# TQFP-DIP.net
KiCad netlist of a schematic drawn in EAGLE
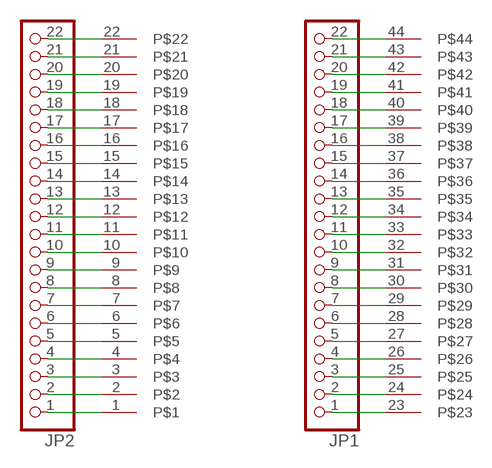
[diagram p0: schematic, sheet 1]

(export (version "E")
  (design (tool "Eeschema 10.0.6"))
  (components
    (comp (ref "JP1")
      (value "PINHD-1X22")
      (footprint "eagle-import:1X22")
      (libsource (lib "eagle-import") (part "PINHD-1X22"))
    )
    (comp (ref "JP2")
      (value "PINHD-1X22")
      (footprint "eagle-import:1X22")
      (libsource (lib "eagle-import") (part "PINHD-1X22"))
    )
    (comp (ref "U$1")
      (value "TQFP44")
      (footprint "eagle-import:TQFP44")
      (libsource (lib "eagle-import") (part "TQFP44"))
    )
  )
  (nets
    (net (code "1") (name "Net-(U$1-P$1)") (class "Default")
      (node (ref "JP2") (pin "1") (pinfunction "1_1") (pintype "passive"))
      (node (ref "U$1") (pin "1") (pinfunction "P$1_1") (pintype "bidirectional"))
    )
    (net (code "2") (name "Net-(U$1-P$2)") (class "Default")
      (node (ref "JP2") (pin "2") (pinfunction "2_2") (pintype "passive"))
      (node (ref "U$1") (pin "2") (pinfunction "P$2_2") (pintype "bidirectional"))
    )
    (net (code "3") (name "Net-(U$1-P$3)") (class "Default")
      (node (ref "JP2") (pin "3") (pinfunction "3_3") (pintype "passive"))
      (node (ref "U$1") (pin "3") (pinfunction "P$3_3") (pintype "bidirectional"))
    )
    (net (code "4") (name "Net-(U$1-P$4)") (class "Default")
      (node (ref "JP2") (pin "4") (pinfunction "4_4") (pintype "passive"))
      (node (ref "U$1") (pin "4") (pinfunction "P$4_4") (pintype "bidirectional"))
    )
    (net (code "5") (name "Net-(U$1-P$5)") (class "Default")
      (node (ref "JP2") (pin "5") (pinfunction "5_5") (pintype "passive"))
      (node (ref "U$1") (pin "5") (pinfunction "P$5_5") (pintype "bidirectional"))
    )
    (net (code "6") (name "Net-(U$1-P$6)") (class "Default")
      (node (ref "JP2") (pin "6") (pinfunction "6_6") (pintype "passive"))
      (node (ref "U$1") (pin "6") (pinfunction "P$6_6") (pintype "bidirectional"))
    )
    (net (code "7") (name "Net-(U$1-P$7)") (class "Default")
      (node (ref "JP2") (pin "7") (pinfunction "7_7") (pintype "passive"))
      (node (ref "U$1") (pin "7") (pinfunction "P$7_7") (pintype "bidirectional"))
    )
    (net (code "8") (name "Net-(U$1-P$8)") (class "Default")
      (node (ref "JP2") (pin "8") (pinfunction "8_8") (pintype "passive"))
      (node (ref "U$1") (pin "8") (pinfunction "P$8_8") (pintype "bidirectional"))
    )
    (net (code "9") (name "Net-(U$1-P$9)") (class "Default")
      (node (ref "JP2") (pin "9") (pinfunction "9_9") (pintype "passive"))
      (node (ref "U$1") (pin "9") (pinfunction "P$9_9") (pintype "bidirectional"))
    )
    (net (code "10") (name "Net-(U$1-P$10)") (class "Default")
      (node (ref "JP2") (pin "10") (pinfunction "10_10") (pintype "passive"))
      (node (ref "U$1") (pin "10") (pinfunction "P$10_10") (pintype "bidirectional"))
    )
    (net (code "11") (name "Net-(U$1-P$11)") (class "Default")
      (node (ref "JP2") (pin "11") (pinfunction "11_11") (pintype "passive"))
      (node (ref "U$1") (pin "11") (pinfunction "P$11_11") (pintype "bidirectional"))
    )
    (net (code "12") (name "Net-(U$1-P$12)") (class "Default")
      (node (ref "JP2") (pin "12") (pinfunction "12_12") (pintype "passive"))
      (node (ref "U$1") (pin "12") (pinfunction "P$12_12") (pintype "bidirectional"))
    )
    (net (code "13") (name "Net-(U$1-P$13)") (class "Default")
      (node (ref "JP2") (pin "13") (pinfunction "13_13") (pintype "passive"))
      (node (ref "U$1") (pin "13") (pinfunction "P$13_13") (pintype "bidirectional"))
    )
    (net (code "14") (name "Net-(U$1-P$14)") (class "Default")
      (node (ref "JP2") (pin "14") (pinfunction "14_14") (pintype "passive"))
      (node (ref "U$1") (pin "14") (pinfunction "P$14_14") (pintype "bidirectional"))
    )
    (net (code "15") (name "Net-(U$1-P$15)") (class "Default")
      (node (ref "JP2") (pin "15") (pinfunction "15_15") (pintype "passive"))
      (node (ref "U$1") (pin "15") (pinfunction "P$15_15") (pintype "bidirectional"))
    )
    (net (code "16") (name "Net-(U$1-P$16)") (class "Default")
      (node (ref "JP2") (pin "16") (pinfunction "16_16") (pintype "passive"))
      (node (ref "U$1") (pin "16") (pinfunction "P$16_16") (pintype "bidirectional"))
    )
    (net (code "17") (name "Net-(U$1-P$17)") (class "Default")
      (node (ref "JP2") (pin "17") (pinfunction "17_17") (pintype "passive"))
      (node (ref "U$1") (pin "17") (pinfunction "P$17_17") (pintype "bidirectional"))
    )
    (net (code "18") (name "Net-(U$1-P$18)") (class "Default")
      (node (ref "JP2") (pin "18") (pinfunction "18_18") (pintype "passive"))
      (node (ref "U$1") (pin "18") (pinfunction "P$18_18") (pintype "bidirectional"))
    )
    (net (code "19") (name "Net-(U$1-P$19)") (class "Default")
      (node (ref "JP2") (pin "19") (pinfunction "19_19") (pintype "passive"))
      (node (ref "U$1") (pin "19") (pinfunction "P$19_19") (pintype "bidirectional"))
    )
    (net (code "20") (name "Net-(U$1-P$20)") (class "Default")
      (node (ref "JP2") (pin "20") (pinfunction "20_20") (pintype "passive"))
      (node (ref "U$1") (pin "20") (pinfunction "P$20_20") (pintype "bidirectional"))
    )
    (net (code "21") (name "Net-(U$1-P$21)") (class "Default")
      (node (ref "JP2") (pin "21") (pinfunction "21_21") (pintype "passive"))
      (node (ref "U$1") (pin "21") (pinfunction "P$21_21") (pintype "bidirectional"))
    )
    (net (code "22") (name "Net-(U$1-P$22)") (class "Default")
      (node (ref "JP2") (pin "22") (pinfunction "22_22") (pintype "passive"))
      (node (ref "U$1") (pin "22") (pinfunction "P$22_22") (pintype "bidirectional"))
    )
    (net (code "23") (name "Net-(U$1-P$23)") (class "Default")
      (node (ref "JP1") (pin "1") (pinfunction "1_1") (pintype "passive"))
      (node (ref "U$1") (pin "23") (pinfunction "P$23_23") (pintype "bidirectional"))
    )
    (net (code "24") (name "Net-(U$1-P$24)") (class "Default")
      (node (ref "JP1") (pin "2") (pinfunction "2_2") (pintype "passive"))
      (node (ref "U$1") (pin "24") (pinfunction "P$24_24") (pintype "bidirectional"))
    )
    (net (code "25") (name "Net-(U$1-P$25)") (class "Default")
      (node (ref "JP1") (pin "3") (pinfunction "3_3") (pintype "passive"))
      (node (ref "U$1") (pin "25") (pinfunction "P$25_25") (pintype "bidirectional"))
    )
    (net (code "26") (name "Net-(U$1-P$26)") (class "Default")
      (node (ref "JP1") (pin "4") (pinfunction "4_4") (pintype "passive"))
      (node (ref "U$1") (pin "26") (pinfunction "P$26_26") (pintype "bidirectional"))
    )
    (net (code "27") (name "Net-(U$1-P$27)") (class "Default")
      (node (ref "JP1") (pin "5") (pinfunction "5_5") (pintype "passive"))
      (node (ref "U$1") (pin "27") (pinfunction "P$27_27") (pintype "bidirectional"))
    )
    (net (code "28") (name "Net-(U$1-P$28)") (class "Default")
      (node (ref "JP1") (pin "6") (pinfunction "6_6") (pintype "passive"))
      (node (ref "U$1") (pin "28") (pinfunction "P$28_28") (pintype "bidirectional"))
    )
    (net (code "29") (name "Net-(U$1-P$29)") (class "Default")
      (node (ref "JP1") (pin "7") (pinfunction "7_7") (pintype "passive"))
      (node (ref "U$1") (pin "29") (pinfunction "P$29_29") (pintype "bidirectional"))
    )
    (net (code "30") (name "Net-(U$1-P$30)") (class "Default")
      (node (ref "JP1") (pin "8") (pinfunction "8_8") (pintype "passive"))
      (node (ref "U$1") (pin "30") (pinfunction "P$30_30") (pintype "bidirectional"))
    )
    (net (code "31") (name "Net-(U$1-P$31)") (class "Default")
      (node (ref "JP1") (pin "9") (pinfunction "9_9") (pintype "passive"))
      (node (ref "U$1") (pin "31") (pinfunction "P$31_31") (pintype "bidirectional"))
    )
    (net (code "32") (name "Net-(U$1-P$32)") (class "Default")
      (node (ref "JP1") (pin "10") (pinfunction "10_10") (pintype "passive"))
      (node (ref "U$1") (pin "32") (pinfunction "P$32_32") (pintype "bidirectional"))
    )
    (net (code "33") (name "Net-(U$1-P$33)") (class "Default")
      (node (ref "JP1") (pin "11") (pinfunction "11_11") (pintype "passive"))
      (node (ref "U$1") (pin "33") (pinfunction "P$33_33") (pintype "bidirectional"))
    )
    (net (code "34") (name "Net-(U$1-P$34)") (class "Default")
      (node (ref "JP1") (pin "12") (pinfunction "12_12") (pintype "passive"))
      (node (ref "U$1") (pin "34") (pinfunction "P$34_34") (pintype "bidirectional"))
    )
    (net (code "35") (name "Net-(U$1-P$35)") (class "Default")
      (node (ref "JP1") (pin "13") (pinfunction "13_13") (pintype "passive"))
      (node (ref "U$1") (pin "35") (pinfunction "P$35_35") (pintype "bidirectional"))
    )
    (net (code "36") (name "Net-(U$1-P$36)") (class "Default")
      (node (ref "JP1") (pin "14") (pinfunction "14_14") (pintype "passive"))
      (node (ref "U$1") (pin "36") (pinfunction "P$36_36") (pintype "bidirectional"))
    )
    (net (code "37") (name "Net-(U$1-P$37)") (class "Default")
      (node (ref "JP1") (pin "15") (pinfunction "15_15") (pintype "passive"))
      (node (ref "U$1") (pin "37") (pinfunction "P$37_37") (pintype "bidirectional"))
    )
    (net (code "38") (name "Net-(U$1-P$38)") (class "Default")
      (node (ref "JP1") (pin "16") (pinfunction "16_16") (pintype "passive"))
      (node (ref "U$1") (pin "38") (pinfunction "P$38_38") (pintype "bidirectional"))
    )
    (net (code "39") (name "Net-(U$1-P$39)") (class "Default")
      (node (ref "JP1") (pin "17") (pinfunction "17_17") (pintype "passive"))
      (node (ref "U$1") (pin "39") (pinfunction "P$39_39") (pintype "bidirectional"))
    )
    (net (code "40") (name "Net-(U$1-P$40)") (class "Default")
      (node (ref "JP1") (pin "18") (pinfunction "18_18") (pintype "passive"))
      (node (ref "U$1") (pin "40") (pinfunction "P$40_40") (pintype "bidirectional"))
    )
    (net (code "41") (name "Net-(U$1-P$41)") (class "Default")
      (node (ref "JP1") (pin "19") (pinfunction "19_19") (pintype "passive"))
      (node (ref "U$1") (pin "41") (pinfunction "P$41_41") (pintype "bidirectional"))
    )
    (net (code "42") (name "Net-(U$1-P$42)") (class "Default")
      (node (ref "JP1") (pin "20") (pinfunction "20_20") (pintype "passive"))
      (node (ref "U$1") (pin "42") (pinfunction "P$42_42") (pintype "bidirectional"))
    )
    (net (code "43") (name "Net-(U$1-P$43)") (class "Default")
      (node (ref "JP1") (pin "21") (pinfunction "21_21") (pintype "passive"))
      (node (ref "U$1") (pin "43") (pinfunction "P$43_43") (pintype "bidirectional"))
    )
    (net (code "44") (name "Net-(U$1-P$44)") (class "Default")
      (node (ref "JP1") (pin "22") (pinfunction "22_22") (pintype "passive"))
      (node (ref "U$1") (pin "44") (pinfunction "P$44_44") (pintype "bidirectional"))
    )
  )
)
